# mini_exp_v1-1-0a.net
KiCad netlist of a schematic drawn in EAGLE
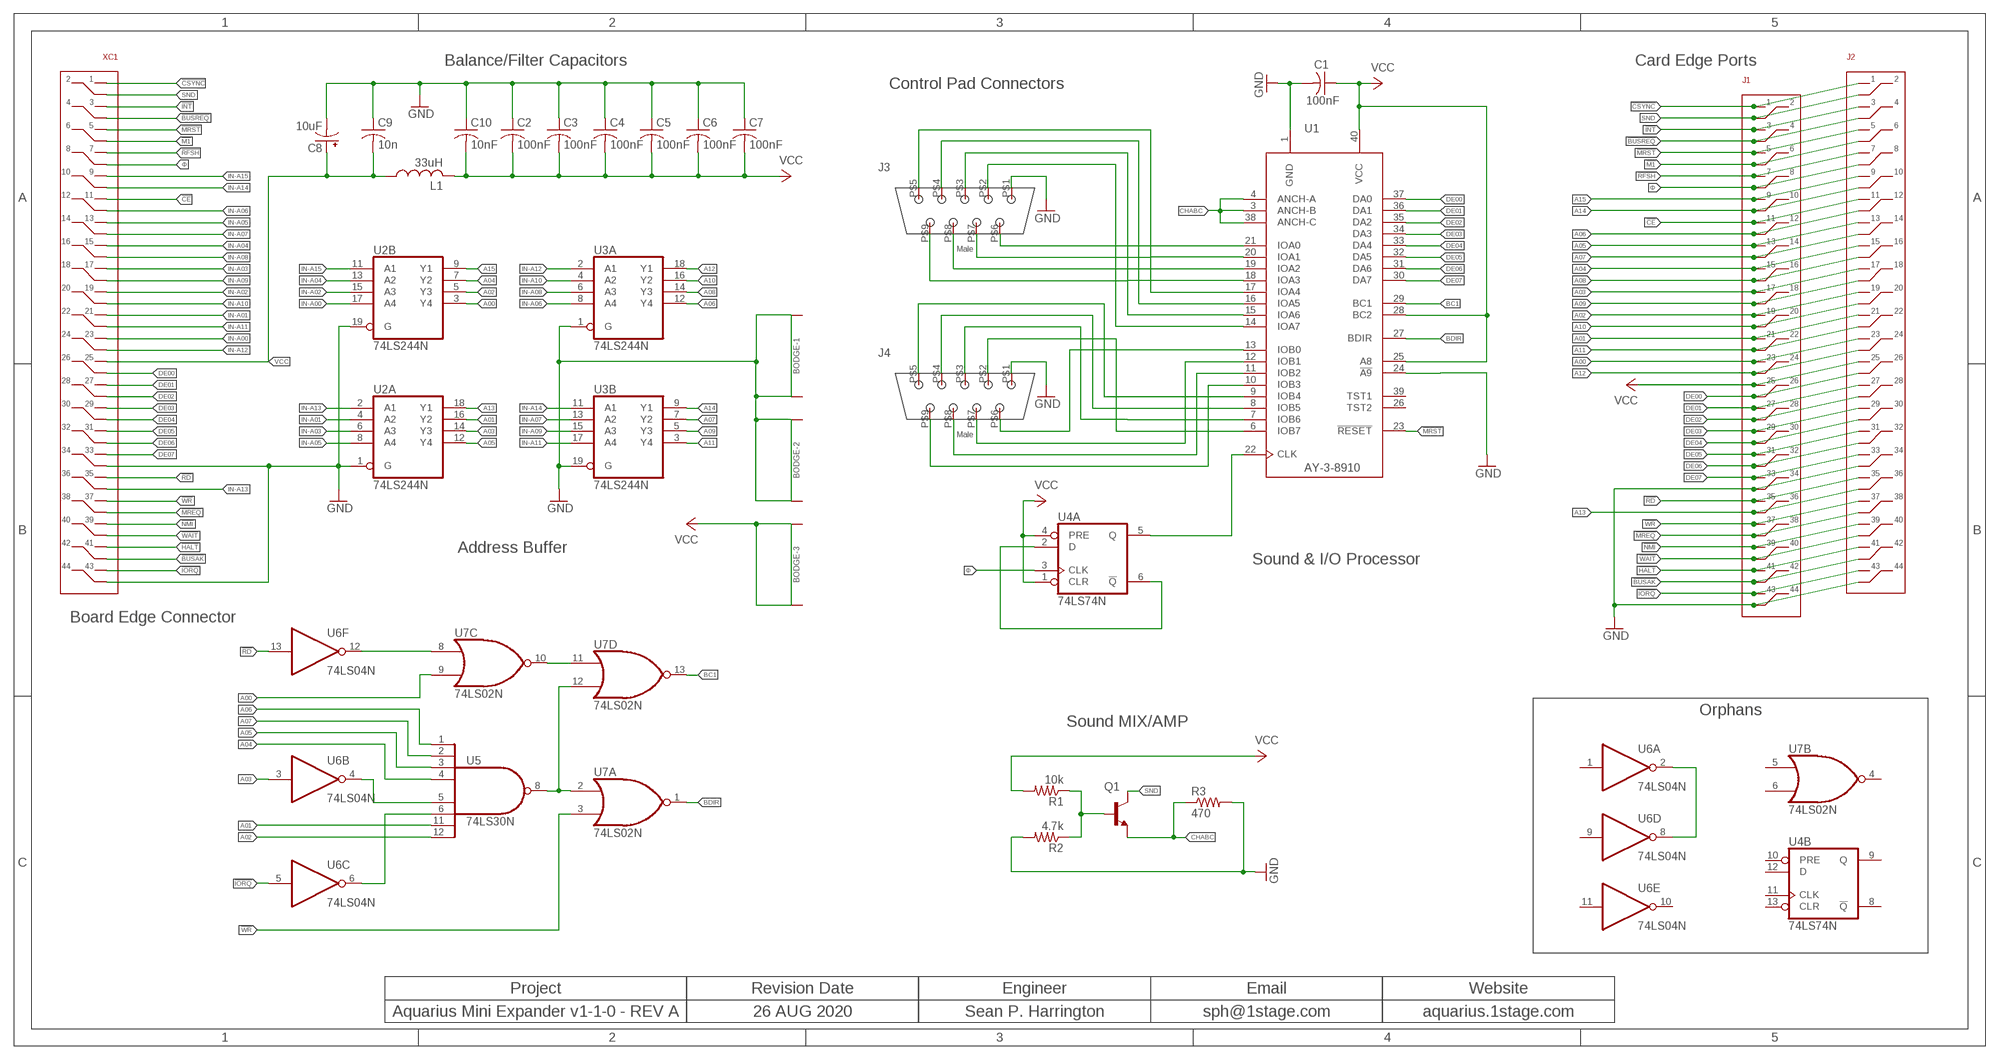
[diagram p0: schematic, sheet 1]

(export (version "E")
  (design (tool "Eeschema 10.0.6"))
  (components
    (comp (ref "C1")
      (value "100nF")
      (footprint "eagle-import:C050-025X095")
      (libsource (lib "eagle-import") (part "C-US050-025X095"))
    )
    (comp (ref "C2")
      (value "100nF")
      (footprint "eagle-import:C050-025X095")
      (libsource (lib "eagle-import") (part "C-US050-025X095"))
    )
    (comp (ref "C3")
      (value "100nF")
      (footprint "eagle-import:C050-025X095")
      (libsource (lib "eagle-import") (part "C-US050-025X095"))
    )
    (comp (ref "C4")
      (value "100nF")
      (footprint "eagle-import:C050-025X095")
      (libsource (lib "eagle-import") (part "C-US050-025X095"))
    )
    (comp (ref "C5")
      (value "100nF")
      (footprint "eagle-import:C050-025X095")
      (libsource (lib "eagle-import") (part "C-US050-025X095"))
    )
    (comp (ref "C6")
      (value "100nF")
      (footprint "eagle-import:C050-025X095")
      (libsource (lib "eagle-import") (part "C-US050-025X095"))
    )
    (comp (ref "C7")
      (value "100nF")
      (footprint "eagle-import:C050-025X095")
      (libsource (lib "eagle-import") (part "C-US050-025X095"))
    )
    (comp (ref "C8")
      (value "10uF")
      (footprint "eagle-import:E22-6")
      (libsource (lib "eagle-import") (part "CPOL-USE22-6AXIAL"))
    )
    (comp (ref "C9")
      (value "10n")
      (footprint "eagle-import:C075-032X103")
      (libsource (lib "eagle-import") (part "C-US075-032X103"))
    )
    (comp (ref "C10")
      (value "10nF")
      (footprint "eagle-import:C075-032X103")
      (libsource (lib "eagle-import") (part "C-US075-032X103"))
    )
    (comp (ref "J1")
      (value "CR22A-44D-2.54DS(70)STRAIGHT")
      (footprint "eagle-import:CR22A-44D-2.54DS(70)")
      (libsource (lib "eagle-import") (part "CR22A-44D-2.54DS(70)STRAIGHT"))
    )
    (comp (ref "J2")
      (value "CR22A-44D-2.54DS(70)STRAIGHT")
      (footprint "eagle-import:CR22A-44D-2.54DS(70)")
      (libsource (lib "eagle-import") (part "CR22A-44D-2.54DS(70)STRAIGHT"))
    )
    (comp (ref "J3")
      (value "DB9-MALE-RA")
      (footprint "eagle-import:DB9-MALE-RA")
      (libsource (lib "eagle-import") (part "DB9-MALE-RA"))
    )
    (comp (ref "J4")
      (value "DB9-MALE-RA")
      (footprint "eagle-import:DB9-MALE-RA")
      (libsource (lib "eagle-import") (part "DB9-MALE-RA"))
    )
    (comp (ref "L1")
      (value "33uH")
      (footprint "eagle-import:0204_5")
      (libsource (lib "eagle-import") (part "L-US0204/5"))
    )
    (comp (ref "Q1")
      (value "-NPN-TO92L")
      (footprint "eagle-import:TO92L")
      (libsource (lib "eagle-import") (part "-NPN-TO92L"))
    )
    (comp (ref "R1")
      (value "10k")
      (footprint "eagle-import:0207_7")
      (libsource (lib "eagle-import") (part "R-US_0207/7"))
    )
    (comp (ref "R2")
      (value "4.7k")
      (footprint "eagle-import:0207_7")
      (libsource (lib "eagle-import") (part "R-US_0207/7"))
    )
    (comp (ref "R3")
      (value "470")
      (footprint "eagle-import:0207_7")
      (libsource (lib "eagle-import") (part "R-US_0207/7"))
    )
    (comp (ref "U1")
      (value "AY-3-8910")
      (footprint "eagle-import:RAD38910-DIL40-6")
      (libsource (lib "eagle-import") (part "RAD38910DIL40-6"))
    )
    (comp (ref "U2")
      (value "74LS244N")
      (footprint "eagle-import:DIL20")
      (libsource (lib "eagle-import") (part "74244NLS"))
    )
    (comp (ref "U3")
      (value "74LS244N")
      (footprint "eagle-import:DIL20")
      (libsource (lib "eagle-import") (part "74244NLS"))
    )
    (comp (ref "U4")
      (value "74LS74N")
      (footprint "eagle-import:DIL14")
      (libsource (lib "eagle-import") (part "7474NLS"))
    )
    (comp (ref "U5")
      (value "74LS30N")
      (footprint "eagle-import:DIL14")
      (libsource (lib "eagle-import") (part "7430NLS"))
    )
    (comp (ref "U6")
      (value "74LS04N")
      (footprint "eagle-import:DIL14")
      (libsource (lib "eagle-import") (part "7404NLS"))
    )
    (comp (ref "U7")
      (value "74LS02N")
      (footprint "eagle-import:DIL14")
      (libsource (lib "eagle-import") (part "7402NLS"))
    )
    (comp (ref "XC1")
      (value "AQ-CART-EDGE")
      (footprint "eagle-import:AQ-CART-EDGE")
      (libsource (lib "eagle-import") (part "AQ-CART-EDGE"))
    )
    (comp (ref "XX01")
      (value "AQ-MX-BODGE-1")
      (footprint "eagle-import:AQ-MX-BODGE-1")
      (libsource (lib "eagle-import") (part "AQ-MX-BODGE-1"))
    )
    (comp (ref "XX02")
      (value "AQ-MX-BODGE-2")
      (footprint "eagle-import:AQ-MX-BODGE-2")
      (libsource (lib "eagle-import") (part "AQ-MX-BODGE-2"))
    )
    (comp (ref "XX03")
      (value "AQ-MX-BODGE-3")
      (footprint "eagle-import:AQ-MX-BODGE-3")
      (libsource (lib "eagle-import") (part "AQ-MX-BODGE-3"))
    )
  )
  (nets
    (net (code "1") (name "/~{BUSAK}") (class "Default")
      (node (ref "J1") (pin "P$42") (pinfunction "X42_P$42") (pintype "bidirectional"))
      (node (ref "J2") (pin "P$42") (pinfunction "X42_P$42") (pintype "bidirectional"))
      (node (ref "XC1") (pin "P$42") (pinfunction "X42_P$42") (pintype "bidirectional"))
    )
    (net (code "2") (name "/~{BUSREQ}") (class "Default")
      (node (ref "J1") (pin "P$4") (pinfunction "X4_P$4") (pintype "bidirectional"))
      (node (ref "J2") (pin "P$4") (pinfunction "X4_P$4") (pintype "bidirectional"))
      (node (ref "XC1") (pin "P$4") (pinfunction "X4_P$4") (pintype "bidirectional"))
    )
    (net (code "3") (name "/~{CE}") (class "Default")
      (node (ref "J1") (pin "P$11") (pinfunction "X11_P$11") (pintype "bidirectional"))
      (node (ref "J2") (pin "P$11") (pinfunction "X11_P$11") (pintype "bidirectional"))
      (node (ref "XC1") (pin "P$11") (pinfunction "X11_P$11") (pintype "bidirectional"))
    )
    (net (code "4") (name "/~{CSYNC}") (class "Default")
      (node (ref "J1") (pin "P$1") (pinfunction "X1_P$1") (pintype "bidirectional"))
      (node (ref "J2") (pin "P$1") (pinfunction "X1_P$1") (pintype "bidirectional"))
      (node (ref "XC1") (pin "P$1") (pinfunction "X1_P$1") (pintype "bidirectional"))
    )
    (net (code "5") (name "/~{HALT}") (class "Default")
      (node (ref "J1") (pin "P$41") (pinfunction "X41_P$41") (pintype "bidirectional"))
      (node (ref "J2") (pin "P$41") (pinfunction "X41_P$41") (pintype "bidirectional"))
      (node (ref "XC1") (pin "P$41") (pinfunction "X41_P$41") (pintype "bidirectional"))
    )
    (net (code "6") (name "/~{INT}") (class "Default")
      (node (ref "J1") (pin "P$3") (pinfunction "X3_P$3") (pintype "bidirectional"))
      (node (ref "J2") (pin "P$3") (pinfunction "X3_P$3") (pintype "bidirectional"))
      (node (ref "XC1") (pin "P$3") (pinfunction "X3_P$3") (pintype "bidirectional"))
    )
    (net (code "7") (name "/~{IORQ}") (class "Default")
      (node (ref "J1") (pin "P$43") (pinfunction "X43_P$43") (pintype "bidirectional"))
      (node (ref "J2") (pin "P$43") (pinfunction "X43_P$43") (pintype "bidirectional"))
      (node (ref "U6") (pin "5") (pinfunction "I_5") (pintype "input"))
      (node (ref "XC1") (pin "P$43") (pinfunction "X43_P$43") (pintype "bidirectional"))
    )
    (net (code "8") (name "/~{M1}") (class "Default")
      (node (ref "J1") (pin "P$6") (pinfunction "X6_P$6") (pintype "bidirectional"))
      (node (ref "J2") (pin "P$6") (pinfunction "X6_P$6") (pintype "bidirectional"))
      (node (ref "XC1") (pin "P$6") (pinfunction "X6_P$6") (pintype "bidirectional"))
    )
    (net (code "9") (name "/~{MREQ}") (class "Default")
      (node (ref "J1") (pin "P$38") (pinfunction "X38_P$38") (pintype "bidirectional"))
      (node (ref "J2") (pin "P$38") (pinfunction "X38_P$38") (pintype "bidirectional"))
      (node (ref "XC1") (pin "P$38") (pinfunction "X38_P$38") (pintype "bidirectional"))
    )
    (net (code "10") (name "/~{MRST}") (class "Default")
      (node (ref "J1") (pin "P$5") (pinfunction "X5_P$5") (pintype "bidirectional"))
      (node (ref "J2") (pin "P$5") (pinfunction "X5_P$5") (pintype "bidirectional"))
      (node (ref "U1") (pin "23") (pinfunction "~{RESET}_23") (pintype "bidirectional"))
      (node (ref "XC1") (pin "P$5") (pinfunction "X5_P$5") (pintype "bidirectional"))
    )
    (net (code "11") (name "/~{NMI}") (class "Default")
      (node (ref "J1") (pin "P$39") (pinfunction "X39_P$39") (pintype "bidirectional"))
      (node (ref "J2") (pin "P$39") (pinfunction "X39_P$39") (pintype "bidirectional"))
      (node (ref "XC1") (pin "P$39") (pinfunction "X39_P$39") (pintype "bidirectional"))
    )
    (net (code "12") (name "/~{RD}") (class "Default")
      (node (ref "J1") (pin "P$35") (pinfunction "X35_P$35") (pintype "bidirectional"))
      (node (ref "J2") (pin "P$35") (pinfunction "X35_P$35") (pintype "bidirectional"))
      (node (ref "U6") (pin "13") (pinfunction "I_13") (pintype "input"))
      (node (ref "XC1") (pin "P$35") (pinfunction "X35_P$35") (pintype "bidirectional"))
    )
    (net (code "13") (name "/~{RFSH}") (class "Default")
      (node (ref "J1") (pin "P$7") (pinfunction "X7_P$7") (pintype "bidirectional"))
      (node (ref "J2") (pin "P$7") (pinfunction "X7_P$7") (pintype "bidirectional"))
      (node (ref "XC1") (pin "P$7") (pinfunction "X7_P$7") (pintype "bidirectional"))
    )
    (net (code "14") (name "/~{WAIT}") (class "Default")
      (node (ref "J1") (pin "P$40") (pinfunction "X40_P$40") (pintype "bidirectional"))
      (node (ref "J2") (pin "P$40") (pinfunction "X40_P$40") (pintype "bidirectional"))
      (node (ref "XC1") (pin "P$40") (pinfunction "X40_P$40") (pintype "bidirectional"))
    )
    (net (code "15") (name "/~{WR}") (class "Default")
      (node (ref "J1") (pin "P$37") (pinfunction "X37_P$37") (pintype "bidirectional"))
      (node (ref "J2") (pin "P$37") (pinfunction "X37_P$37") (pintype "bidirectional"))
      (node (ref "U7") (pin "3") (pinfunction "I1_3") (pintype "input"))
      (node (ref "XC1") (pin "P$37") (pinfunction "X37_P$37") (pintype "bidirectional"))
    )
    (net (code "16") (name "A00") (class "Default")
      (node (ref "J1") (pin "P$23") (pinfunction "X23_P$23") (pintype "bidirectional"))
      (node (ref "J2") (pin "P$23") (pinfunction "X23_P$23") (pintype "bidirectional"))
      (node (ref "U2") (pin "3") (pinfunction "Y4_3") (pintype "tri_state"))
      (node (ref "U7") (pin "9") (pinfunction "I1_9") (pintype "input"))
    )
    (net (code "17") (name "A01") (class "Default")
      (node (ref "J1") (pin "P$21") (pinfunction "X21_P$21") (pintype "bidirectional"))
      (node (ref "J2") (pin "P$21") (pinfunction "X21_P$21") (pintype "bidirectional"))
      (node (ref "U2") (pin "16") (pinfunction "Y2_16") (pintype "tri_state"))
      (node (ref "U5") (pin "11") (pinfunction "I6_11") (pintype "input"))
    )
    (net (code "18") (name "A02") (class "Default")
      (node (ref "J1") (pin "P$19") (pinfunction "X19_P$19") (pintype "bidirectional"))
      (node (ref "J2") (pin "P$19") (pinfunction "X19_P$19") (pintype "bidirectional"))
      (node (ref "U2") (pin "5") (pinfunction "Y3_5") (pintype "tri_state"))
      (node (ref "U5") (pin "12") (pinfunction "I7_12") (pintype "input"))
    )
    (net (code "19") (name "A03") (class "Default")
      (node (ref "J1") (pin "P$17") (pinfunction "X17_P$17") (pintype "bidirectional"))
      (node (ref "J2") (pin "P$17") (pinfunction "X17_P$17") (pintype "bidirectional"))
      (node (ref "U2") (pin "14") (pinfunction "Y3_14") (pintype "tri_state"))
      (node (ref "U6") (pin "3") (pinfunction "I_3") (pintype "input"))
    )
    (net (code "20") (name "A04") (class "Default")
      (node (ref "J1") (pin "P$15") (pinfunction "X15_P$15") (pintype "bidirectional"))
      (node (ref "J2") (pin "P$15") (pinfunction "X15_P$15") (pintype "bidirectional"))
      (node (ref "U2") (pin "7") (pinfunction "Y2_7") (pintype "tri_state"))
      (node (ref "U5") (pin "4") (pinfunction "I3_4") (pintype "input"))
    )
    (net (code "21") (name "A05") (class "Default")
      (node (ref "J1") (pin "P$13") (pinfunction "X13_P$13") (pintype "bidirectional"))
      (node (ref "J2") (pin "P$13") (pinfunction "X13_P$13") (pintype "bidirectional"))
      (node (ref "U2") (pin "12") (pinfunction "Y4_12") (pintype "tri_state"))
      (node (ref "U5") (pin "3") (pinfunction "I2_3") (pintype "input"))
    )
    (net (code "22") (name "A06") (class "Default")
      (node (ref "J1") (pin "P$12") (pinfunction "X12_P$12") (pintype "bidirectional"))
      (node (ref "J2") (pin "P$12") (pinfunction "X12_P$12") (pintype "bidirectional"))
      (node (ref "U3") (pin "12") (pinfunction "Y4_12") (pintype "tri_state"))
      (node (ref "U5") (pin "1") (pinfunction "I0_1") (pintype "input"))
    )
    (net (code "23") (name "A07") (class "Default")
      (node (ref "J1") (pin "P$14") (pinfunction "X14_P$14") (pintype "bidirectional"))
      (node (ref "J2") (pin "P$14") (pinfunction "X14_P$14") (pintype "bidirectional"))
      (node (ref "U3") (pin "7") (pinfunction "Y2_7") (pintype "tri_state"))
      (node (ref "U5") (pin "2") (pinfunction "I1_2") (pintype "input"))
    )
    (net (code "24") (name "A08") (class "Default")
      (node (ref "J1") (pin "P$16") (pinfunction "X16_P$16") (pintype "bidirectional"))
      (node (ref "J2") (pin "P$16") (pinfunction "X16_P$16") (pintype "bidirectional"))
      (node (ref "U3") (pin "14") (pinfunction "Y3_14") (pintype "tri_state"))
    )
    (net (code "25") (name "A09") (class "Default")
      (node (ref "J1") (pin "P$18") (pinfunction "X18_P$18") (pintype "bidirectional"))
      (node (ref "J2") (pin "P$18") (pinfunction "X18_P$18") (pintype "bidirectional"))
      (node (ref "U3") (pin "5") (pinfunction "Y3_5") (pintype "tri_state"))
    )
    (net (code "26") (name "A10") (class "Default")
      (node (ref "J1") (pin "P$20") (pinfunction "X20_P$20") (pintype "bidirectional"))
      (node (ref "J2") (pin "P$20") (pinfunction "X20_P$20") (pintype "bidirectional"))
      (node (ref "U3") (pin "16") (pinfunction "Y2_16") (pintype "tri_state"))
    )
    (net (code "27") (name "A11") (class "Default")
      (node (ref "J1") (pin "P$22") (pinfunction "X22_P$22") (pintype "bidirectional"))
      (node (ref "J2") (pin "P$22") (pinfunction "X22_P$22") (pintype "bidirectional"))
      (node (ref "U3") (pin "3") (pinfunction "Y4_3") (pintype "tri_state"))
    )
    (net (code "28") (name "A12") (class "Default")
      (node (ref "J1") (pin "P$24") (pinfunction "X24_P$24") (pintype "bidirectional"))
      (node (ref "J2") (pin "P$24") (pinfunction "X24_P$24") (pintype "bidirectional"))
      (node (ref "U3") (pin "18") (pinfunction "Y1_18") (pintype "tri_state"))
    )
    (net (code "29") (name "A13") (class "Default")
      (node (ref "J1") (pin "P$36") (pinfunction "X36_P$36") (pintype "bidirectional"))
      (node (ref "J2") (pin "P$36") (pinfunction "X36_P$36") (pintype "bidirectional"))
      (node (ref "U2") (pin "18") (pinfunction "Y1_18") (pintype "tri_state"))
    )
    (net (code "30") (name "A14") (class "Default")
      (node (ref "J1") (pin "P$10") (pinfunction "X10_P$10") (pintype "bidirectional"))
      (node (ref "J2") (pin "P$10") (pinfunction "X10_P$10") (pintype "bidirectional"))
      (node (ref "U3") (pin "9") (pinfunction "Y1_9") (pintype "tri_state"))
    )
    (net (code "31") (name "A15") (class "Default")
      (node (ref "J1") (pin "P$9") (pinfunction "X9_P$9") (pintype "bidirectional"))
      (node (ref "J2") (pin "P$9") (pinfunction "X9_P$9") (pintype "bidirectional"))
      (node (ref "U2") (pin "9") (pinfunction "Y1_9") (pintype "tri_state"))
    )
    (net (code "32") (name "BC1") (class "Default")
      (node (ref "U1") (pin "29") (pinfunction "BC1_29") (pintype "bidirectional"))
      (node (ref "U7") (pin "13") (pinfunction "O_13") (pintype "output"))
    )
    (net (code "33") (name "BDIR") (class "Default")
      (node (ref "U1") (pin "27") (pinfunction "BDIR_27") (pintype "bidirectional"))
      (node (ref "U7") (pin "1") (pinfunction "O_1") (pintype "output"))
    )
    (net (code "34") (name "CHABC") (class "Default")
      (node (ref "Q1") (pin "1") (pinfunction "E_1") (pintype "passive"))
      (node (ref "R3") (pin "1") (pinfunction "1_1") (pintype "passive"))
      (node (ref "U1") (pin "3") (pinfunction "ANCH-B_3") (pintype "bidirectional"))
      (node (ref "U1") (pin "38") (pinfunction "ANCH-C_38") (pintype "bidirectional"))
      (node (ref "U1") (pin "4") (pinfunction "ANCH-A_4") (pintype "bidirectional"))
    )
    (net (code "35") (name "DE00") (class "Default")
      (node (ref "J1") (pin "P$26") (pinfunction "X26_P$26") (pintype "bidirectional"))
      (node (ref "J2") (pin "P$26") (pinfunction "X26_P$26") (pintype "bidirectional"))
      (node (ref "U1") (pin "37") (pinfunction "DA0_37") (pintype "bidirectional"))
      (node (ref "XC1") (pin "P$26") (pinfunction "X26_P$26") (pintype "bidirectional"))
    )
    (net (code "36") (name "DE01") (class "Default")
      (node (ref "J1") (pin "P$27") (pinfunction "X27_P$27") (pintype "bidirectional"))
      (node (ref "J2") (pin "P$27") (pinfunction "X27_P$27") (pintype "bidirectional"))
      (node (ref "U1") (pin "36") (pinfunction "DA1_36") (pintype "bidirectional"))
      (node (ref "XC1") (pin "P$27") (pinfunction "X27_P$27") (pintype "bidirectional"))
    )
    (net (code "37") (name "DE02") (class "Default")
      (node (ref "J1") (pin "P$28") (pinfunction "X28_P$28") (pintype "bidirectional"))
      (node (ref "J2") (pin "P$28") (pinfunction "X28_P$28") (pintype "bidirectional"))
      (node (ref "U1") (pin "35") (pinfunction "DA2_35") (pintype "bidirectional"))
      (node (ref "XC1") (pin "P$28") (pinfunction "X28_P$28") (pintype "bidirectional"))
    )
    (net (code "38") (name "DE03") (class "Default")
      (node (ref "J1") (pin "P$29") (pinfunction "X29_P$29") (pintype "bidirectional"))
      (node (ref "J2") (pin "P$29") (pinfunction "X29_P$29") (pintype "bidirectional"))
      (node (ref "U1") (pin "34") (pinfunction "DA3_34") (pintype "bidirectional"))
      (node (ref "XC1") (pin "P$29") (pinfunction "X29_P$29") (pintype "bidirectional"))
    )
    (net (code "39") (name "DE04") (class "Default")
      (node (ref "J1") (pin "P$30") (pinfunction "X30_P$30") (pintype "bidirectional"))
      (node (ref "J2") (pin "P$30") (pinfunction "X30_P$30") (pintype "bidirectional"))
      (node (ref "U1") (pin "33") (pinfunction "DA4_33") (pintype "bidirectional"))
      (node (ref "XC1") (pin "P$30") (pinfunction "X30_P$30") (pintype "bidirectional"))
    )
    (net (code "40") (name "DE05") (class "Default")
      (node (ref "J1") (pin "P$31") (pinfunction "X31_P$31") (pintype "bidirectional"))
      (node (ref "J2") (pin "P$31") (pinfunction "X31_P$31") (pintype "bidirectional"))
      (node (ref "U1") (pin "32") (pinfunction "DA5_32") (pintype "bidirectional"))
      (node (ref "XC1") (pin "P$31") (pinfunction "X31_P$31") (pintype "bidirectional"))
    )
    (net (code "41") (name "DE06") (class "Default")
      (node (ref "J1") (pin "P$32") (pinfunction "X32_P$32") (pintype "bidirectional"))
      (node (ref "J2") (pin "P$32") (pinfunction "X32_P$32") (pintype "bidirectional"))
      (node (ref "U1") (pin "31") (pinfunction "DA6_31") (pintype "bidirectional"))
      (node (ref "XC1") (pin "P$32") (pinfunction "X32_P$32") (pintype "bidirectional"))
    )
    (net (code "42") (name "DE07") (class "Default")
      (node (ref "J1") (pin "P$33") (pinfunction "X33_P$33") (pintype "bidirectional"))
      (node (ref "J2") (pin "P$33") (pinfunction "X33_P$33") (pintype "bidirectional"))
      (node (ref "U1") (pin "30") (pinfunction "DA7_30") (pintype "bidirectional"))
      (node (ref "XC1") (pin "P$33") (pinfunction "X33_P$33") (pintype "bidirectional"))
    )
    (net (code "43") (name "GND") (class "Default")
      (node (ref "C1") (pin "2") (pinfunction "2_2") (pintype "passive"))
      (node (ref "C10") (pin "1") (pinfunction "1_1") (pintype "passive"))
      (node (ref "C2") (pin "1") (pinfunction "1_1") (pintype "passive"))
      (node (ref "C3") (pin "1") (pinfunction "1_1") (pintype "passive"))
      (node (ref "C4") (pin "1") (pinfunction "1_1") (pintype "passive"))
      (node (ref "C5") (pin "1") (pinfunction "1_1") (pintype "passive"))
      (node (ref "C6") (pin "1") (pinfunction "1_1") (pintype "passive"))
      (node (ref "C7") (pin "1") (pinfunction "1_1") (pintype "passive"))
      (node (ref "C8") (pin "-") (pinfunction "-_-") (pintype "passive"))
      (node (ref "C9") (pin "1") (pinfunction "1_1") (pintype "passive"))
      (node (ref "J1") (pin "P$34") (pinfunction "X34_P$34") (pintype "bidirectional"))
      (node (ref "J1") (pin "P$44") (pinfunction "X44_P$44") (pintype "bidirectional"))
      (node (ref "J2") (pin "P$34") (pinfunction "X34_P$34") (pintype "bidirectional"))
      (node (ref "J2") (pin "P$44") (pinfunction "X44_P$44") (pintype "bidirectional"))
      (node (ref "J3") (pin "P$1") (pinfunction "P$1_P$1") (pintype "bidirectional"))
      (node (ref "J4") (pin "P$1") (pinfunction "P$1_P$1") (pintype "bidirectional"))
      (node (ref "R2") (pin "2") (pinfunction "2_2") (pintype "passive"))
      (node (ref "R3") (pin "2") (pinfunction "2_2") (pintype "passive"))
      (node (ref "U1") (pin "1") (pinfunction "GND_1") (pintype "power_in"))
      (node (ref "U1") (pin "24") (pinfunction "~{A9}_24") (pintype "bidirectional"))
      (node (ref "U2") (pin "1") (pinfunction "G_1") (pintype "input"))
      (node (ref "U2") (pin "19") (pinfunction "G_19") (pintype "input"))
      (node (ref "U3") (pin "1") (pinfunction "G_1") (pintype "input"))
      (node (ref "U3") (pin "19") (pinfunction "G_19") (pintype "input"))
      (node (ref "XC1") (pin "P$34") (pinfunction "X34_P$34") (pintype "bidirectional"))
      (node (ref "XC1") (pin "P$44") (pinfunction "X44_P$44") (pintype "bidirectional"))
      (node (ref "XX01") (pin "P$1") (pinfunction "P$1_P$1") (pintype "bidirectional"))
      (node (ref "XX01") (pin "P$2") (pinfunction "P$2_P$2") (pintype "bidirectional"))
      (node (ref "XX02") (pin "P$1") (pinfunction "P$1_P$1") (pintype "bidirectional"))
      (node (ref "XX02") (pin "P$2") (pinfunction "P$2_P$2") (pintype "bidirectional"))
    )
    (net (code "44") (name "IN-A00") (class "Default")
      (node (ref "U2") (pin "17") (pinfunction "A4_17") (pintype "input"))
      (node (ref "XC1") (pin "P$23") (pinfunction "X23_P$23") (pintype "bidirectional"))
    )
    (net (code "45") (name "IN-A01") (class "Default")
      (node (ref "U2") (pin "4") (pinfunction "A2_4") (pintype "input"))
      (node (ref "XC1") (pin "P$21") (pinfunction "X21_P$21") (pintype "bidirectional"))
    )
    (net (code "46") (name "IN-A02") (class "Default")
      (node (ref "U2") (pin "15") (pinfunction "A3_15") (pintype "input"))
      (node (ref "XC1") (pin "P$19") (pinfunction "X19_P$19") (pintype "bidirectional"))
    )
    (net (code "47") (name "IN-A03") (class "Default")
      (node (ref "U2") (pin "6") (pinfunction "A3_6") (pintype "input"))
      (node (ref "XC1") (pin "P$17") (pinfunction "X17_P$17") (pintype "bidirectional"))
    )
    (net (code "48") (name "IN-A04") (class "Default")
      (node (ref "U2") (pin "13") (pinfunction "A2_13") (pintype "input"))
      (node (ref "XC1") (pin "P$15") (pinfunction "X15_P$15") (pintype "bidirectional"))
    )
    (net (code "49") (name "IN-A05") (class "Default")
      (node (ref "U2") (pin "8") (pinfunction "A4_8") (pintype "input"))
      (node (ref "XC1") (pin "P$13") (pinfunction "X13_P$13") (pintype "bidirectional"))
    )
    (net (code "50") (name "IN-A06") (class "Default")
      (node (ref "U3") (pin "8") (pinfunction "A4_8") (pintype "input"))
      (node (ref "XC1") (pin "P$12") (pinfunction "X12_P$12") (pintype "bidirectional"))
    )
    (net (code "51") (name "IN-A07") (class "Default")
      (node (ref "U3") (pin "13") (pinfunction "A2_13") (pintype "input"))
      (node (ref "XC1") (pin "P$14") (pinfunction "X14_P$14") (pintype "bidirectional"))
    )
    (net (code "52") (name "IN-A08") (class "Default")
      (node (ref "U3") (pin "6") (pinfunction "A3_6") (pintype "input"))
      (node (ref "XC1") (pin "P$16") (pinfunction "X16_P$16") (pintype "bidirectional"))
    )
    (net (code "53") (name "IN-A09") (class "Default")
      (node (ref "U3") (pin "15") (pinfunction "A3_15") (pintype "input"))
      (node (ref "XC1") (pin "P$18") (pinfunction "X18_P$18") (pintype "bidirectional"))
    )
    (net (code "54") (name "IN-A10") (class "Default")
      (node (ref "U3") (pin "4") (pinfunction "A2_4") (pintype "input"))
      (node (ref "XC1") (pin "P$20") (pinfunction "X20_P$20") (pintype "bidirectional"))
    )
    (net (code "55") (name "IN-A11") (class "Default")
      (node (ref "U3") (pin "17") (pinfunction "A4_17") (pintype "input"))
      (node (ref "XC1") (pin "P$22") (pinfunction "X22_P$22") (pintype "bidirectional"))
    )
    (net (code "56") (name "IN-A12") (class "Default")
      (node (ref "U3") (pin "2") (pinfunction "A1_2") (pintype "input"))
      (node (ref "XC1") (pin "P$24") (pinfunction "X24_P$24") (pintype "bidirectional"))
    )
    (net (code "57") (name "IN-A13") (class "Default")
      (node (ref "U2") (pin "2") (pinfunction "A1_2") (pintype "input"))
      (node (ref "XC1") (pin "P$36") (pinfunction "X36_P$36") (pintype "bidirectional"))
    )
    (net (code "58") (name "IN-A14") (class "Default")
      (node (ref "U3") (pin "11") (pinfunction "A1_11") (pintype "input"))
      (node (ref "XC1") (pin "P$10") (pinfunction "X10_P$10") (pintype "bidirectional"))
    )
    (net (code "59") (name "IN-A15") (class "Default")
      (node (ref "U2") (pin "11") (pinfunction "A1_11") (pintype "input"))
      (node (ref "XC1") (pin "P$9") (pinfunction "X9_P$9") (pintype "bidirectional"))
    )
    (net (code "60") (name "Net-(Q1-B)") (class "Default")
      (node (ref "Q1") (pin "2") (pinfunction "B_2") (pintype "passive"))
      (node (ref "R1") (pin "1") (pinfunction "1_1") (pintype "passive"))
      (node (ref "R2") (pin "1") (pinfunction "1_1") (pintype "passive"))
    )
    (net (code "61") (name "Net-(U1-CLK)") (class "Default")
      (node (ref "U1") (pin "22") (pinfunction "CLK_22") (pintype "input"))
      (node (ref "U4") (pin "5") (pinfunction "Q_5") (pintype "output"))
    )
    (net (code "62") (name "Net-(U1-IOA0)") (class "Default")
      (node (ref "J3") (pin "P$6") (pinfunction "P$6_P$6") (pintype "bidirectional"))
      (node (ref "U1") (pin "21") (pinfunction "IOA0_21") (pintype "bidirectional"))
    )
    (net (code "63") (name "Net-(U1-IOA1)") (class "Default")
      (node (ref "J3") (pin "P$7") (pinfunction "P$7_P$7") (pintype "bidirectional"))
      (node (ref "U1") (pin "20") (pinfunction "IOA1_20") (pintype "bidirectional"))
    )
    (net (code "64") (name "Net-(U1-IOA2)") (class "Default")
      (node (ref "J3") (pin "P$8") (pinfunction "P$8_P$8") (pintype "bidirectional"))
      (node (ref "U1") (pin "19") (pinfunction "IOA2_19") (pintype "bidirectional"))
    )
    (net (code "65") (name "Net-(U1-IOA3)") (class "Default")
      (node (ref "J3") (pin "P$9") (pinfunction "P$9_P$9") (pintype "bidirectional"))
      (node (ref "U1") (pin "18") (pinfunction "IOA3_18") (pintype "bidirectional"))
    )
    (net (code "66") (name "Net-(U1-IOA4)") (class "Default")
      (node (ref "J3") (pin "P$5") (pinfunction "P$5_P$5") (pintype "bidirectional"))
      (node (ref "U1") (pin "17") (pinfunction "IOA4_17") (pintype "bidirectional"))
    )
    (net (code "67") (name "Net-(U1-IOA5)") (class "Default")
      (node (ref "J3") (pin "P$4") (pinfunction "P$4_P$4") (pintype "bidirectional"))
      (node (ref "U1") (pin "16") (pinfunction "IOA5_16") (pintype "bidirectional"))
    )
    (net (code "68") (name "Net-(U1-IOA6)") (class "Default")
      (node (ref "J3") (pin "P$3") (pinfunction "P$3_P$3") (pintype "bidirectional"))
      (node (ref "U1") (pin "15") (pinfunction "IOA6_15") (pintype "bidirectional"))
    )
    (net (code "69") (name "Net-(U1-IOA7)") (class "Default")
      (node (ref "J3") (pin "P$2") (pinfunction "P$2_P$2") (pintype "bidirectional"))
      (node (ref "U1") (pin "14") (pinfunction "IOA7_14") (pintype "bidirectional"))
    )
    (net (code "70") (name "Net-(U1-IOB0)") (class "Default")
      (node (ref "J4") (pin "P$6") (pinfunction "P$6_P$6") (pintype "bidirectional"))
      (node (ref "U1") (pin "13") (pinfunction "IOB0_13") (pintype "bidirectional"))
    )
    (net (code "71") (name "Net-(U1-IOB1)") (class "Default")
      (node (ref "J4") (pin "P$7") (pinfunction "P$7_P$7") (pintype "bidirectional"))
      (node (ref "U1") (pin "12") (pinfunction "IOB1_12") (pintype "bidirectional"))
    )
    (net (code "72") (name "Net-(U1-IOB2)") (class "Default")
      (node (ref "J4") (pin "P$8") (pinfunction "P$8_P$8") (pintype "bidirectional"))
      (node (ref "U1") (pin "11") (pinfunction "IOB2_11") (pintype "bidirectional"))
    )
    (net (code "73") (name "Net-(U1-IOB3)") (class "Default")
      (node (ref "J4") (pin "P$9") (pinfunction "P$9_P$9") (pintype "bidirectional"))
      (node (ref "U1") (pin "10") (pinfunction "IOB3_10") (pintype "bidirectional"))
    )
    (net (code "74") (name "Net-(U1-IOB4)") (class "Default")
      (node (ref "J4") (pin "P$5") (pinfunction "P$5_P$5") (pintype "bidirectional"))
      (node (ref "U1") (pin "9") (pinfunction "IOB4_9") (pintype "bidirectional"))
    )
    (net (code "75") (name "Net-(U1-IOB5)") (class "Default")
      (node (ref "J4") (pin "P$4") (pinfunction "P$4_P$4") (pintype "bidirectional"))
      (node (ref "U1") (pin "8") (pinfunction "IOB5_8") (pintype "bidirectional"))
    )
    (net (code "76") (name "Net-(U1-IOB6)") (class "Default")
      (node (ref "J4") (pin "P$3") (pinfunction "P$3_P$3") (pintype "bidirectional"))
      (node (ref "U1") (pin "7") (pinfunction "IOB6_7") (pintype "bidirectional"))
    )
    (net (code "77") (name "Net-(U1-IOB7)") (class "Default")
      (node (ref "J4") (pin "P$2") (pinfunction "P$2_P$2") (pintype "bidirectional"))
      (node (ref "U1") (pin "6") (pinfunction "IOB7_6") (pintype "bidirectional"))
    )
    (net (code "78") (name "Net-(U4A-D)") (class "Default")
      (node (ref "U4") (pin "2") (pinfunction "D_2") (pintype "input"))
      (node (ref "U4") (pin "6") (pinfunction "~{Q}_6") (pintype "output"))
    )
    (net (code "79") (name "Net-(U5A-I4)") (class "Default")
      (node (ref "U5") (pin "5") (pinfunction "I4_5") (pintype "input"))
      (node (ref "U6") (pin "4") (pinfunction "O_4") (pintype "output"))
    )
    (net (code "80") (name "Net-(U5A-I5)") (class "Default")
      (node (ref "U5") (pin "6") (pinfunction "I5_6") (pintype "input"))
      (node (ref "U6") (pin "6") (pinfunction "O_6") (pintype "output"))
    )
    (net (code "81") (name "Net-(U5A-O)") (class "Default")
      (node (ref "U5") (pin "8") (pinfunction "O_8") (pintype "output"))
      (node (ref "U7") (pin "12") (pinfunction "I1_12") (pintype "input"))
      (node (ref "U7") (pin "2") (pinfunction "I0_2") (pintype "input"))
    )
    (net (code "82") (name "Net-(U6A-O)") (class "Default")
      (node (ref "U6") (pin "2") (pinfunction "O_2") (pintype "output"))
      (node (ref "U6") (pin "8") (pinfunction "O_8") (pintype "output"))
    )
    (net (code "83") (name "Net-(U6F-O)") (class "Default")
      (node (ref "U6") (pin "12") (pinfunction "O_12") (pintype "output"))
      (node (ref "U7") (pin "8") (pinfunction "I0_8") (pintype "input"))
    )
    (net (code "84") (name "Net-(U7C-O)") (class "Default")
      (node (ref "U7") (pin "10") (pinfunction "O_10") (pintype "output"))
      (node (ref "U7") (pin "11") (pinfunction "I0_11") (pintype "input"))
    )
    (net (code "85") (name "SND") (class "Default")
      (node (ref "J1") (pin "P$2") (pinfunction "X2_P$2") (pintype "bidirectional"))
      (node (ref "J2") (pin "P$2") (pinfunction "X2_P$2") (pintype "bidirectional"))
      (node (ref "Q1") (pin "3") (pinfunction "C_3") (pintype "passive"))
      (node (ref "XC1") (pin "P$2") (pinfunction "X2_P$2") (pintype "bidirectional"))
    )
    (net (code "86") (name "VCC") (class "Default")
      (node (ref "C1") (pin "1") (pinfunction "1_1") (pintype "passive"))
      (node (ref "C10") (pin "2") (pinfunction "2_2") (pintype "passive"))
      (node (ref "C2") (pin "2") (pinfunction "2_2") (pintype "passive"))
      (node (ref "C3") (pin "2") (pinfunction "2_2") (pintype "passive"))
      (node (ref "C4") (pin "2") (pinfunction "2_2") (pintype "passive"))
      (node (ref "C5") (pin "2") (pinfunction "2_2") (pintype "passive"))
      (node (ref "C6") (pin "2") (pinfunction "2_2") (pintype "passive"))
      (node (ref "C7") (pin "2") (pinfunction "2_2") (pintype "passive"))
      (node (ref "C8") (pin "+") (pinfunction "+_+") (pintype "passive"))
      (node (ref "C9") (pin "2") (pinfunction "2_2") (pintype "passive"))
      (node (ref "J1") (pin "P$25") (pinfunction "X25_P$25") (pintype "bidirectional"))
      (node (ref "J2") (pin "P$25") (pinfunction "X25_P$25") (pintype "bidirectional"))
      (node (ref "L1") (pin "1") (pinfunction "1_1") (pintype "passive"))
      (node (ref "L1") (pin "2") (pinfunction "2_2") (pintype "passive"))
      (node (ref "R1") (pin "2") (pinfunction "2_2") (pintype "passive"))
      (node (ref "U1") (pin "25") (pinfunction "A8_25") (pintype "bidirectional"))
      (node (ref "U1") (pin "28") (pinfunction "BC2_28") (pintype "bidirectional"))
      (node (ref "U1") (pin "40") (pinfunction "VCC_40") (pintype "power_in"))
      (node (ref "U4") (pin "1") (pinfunction "CLR_1") (pintype "input"))
      (node (ref "U4") (pin "4") (pinfunction "PRE_4") (pintype "input"))
      (node (ref "XC1") (pin "P$25") (pinfunction "X25_P$25") (pintype "bidirectional"))
      (node (ref "XX03") (pin "P$1") (pinfunction "P$1_P$1") (pintype "bidirectional"))
      (node (ref "XX03") (pin "P$2") (pinfunction "P$2_P$2") (pintype "bidirectional"))
    )
    (net (code "87") (name "unconnected-(U1-TST1-Pad39)") (class "Default")
      (node (ref "U1") (pin "39") (pinfunction "TST1_39") (pintype "bidirectional"))
    )
    (net (code "88") (name "unconnected-(U1-TST2-Pad26)") (class "Default")
      (node (ref "U1") (pin "26") (pinfunction "TST2_26") (pintype "bidirectional"))
    )
    (net (code "89") (name "unconnected-(U4B-CLK-Pad11)") (class "Default")
      (node (ref "U4") (pin "11") (pinfunction "CLK_11") (pintype "input"))
    )
    (net (code "90") (name "unconnected-(U4B-CLR-Pad13)") (class "Default")
      (node (ref "U4") (pin "13") (pinfunction "CLR_13") (pintype "input"))
    )
    (net (code "91") (name "unconnected-(U4B-D-Pad12)") (class "Default")
      (node (ref "U4") (pin "12") (pinfunction "D_12") (pintype "input"))
    )
    (net (code "92") (name "unconnected-(U4B-PRE-Pad10)") (class "Default")
      (node (ref "U4") (pin "10") (pinfunction "PRE_10") (pintype "input"))
    )
    (net (code "93") (name "unconnected-(U4B-Q-Pad9)") (class "Default")
      (node (ref "U4") (pin "9") (pinfunction "Q_9") (pintype "output"))
    )
    (net (code "94") (name "unconnected-(U4B-~{Q}-Pad8)") (class "Default")
      (node (ref "U4") (pin "8") (pinfunction "~{Q}_8") (pintype "output"))
    )
    (net (code "95") (name "unconnected-(U6A-I-Pad1)") (class "Default")
      (node (ref "U6") (pin "1") (pinfunction "I_1") (pintype "input"))
    )
    (net (code "96") (name "unconnected-(U6D-I-Pad9)") (class "Default")
      (node (ref "U6") (pin "9") (pinfunction "I_9") (pintype "input"))
    )
    (net (code "97") (name "unconnected-(U6E-I-Pad11)") (class "Default")
      (node (ref "U6") (pin "11") (pinfunction "I_11") (pintype "input"))
    )
    (net (code "98") (name "unconnected-(U6E-O-Pad10)") (class "Default")
      (node (ref "U6") (pin "10") (pinfunction "O_10") (pintype "output"))
    )
    (net (code "99") (name "unconnected-(U7B-I0-Pad5)") (class "Default")
      (node (ref "U7") (pin "5") (pinfunction "I0_5") (pintype "input"))
    )
    (net (code "100") (name "unconnected-(U7B-I1-Pad6)") (class "Default")
      (node (ref "U7") (pin "6") (pinfunction "I1_6") (pintype "input"))
    )
    (net (code "101") (name "unconnected-(U7B-O-Pad4)") (class "Default")
      (node (ref "U7") (pin "4") (pinfunction "O_4") (pintype "output"))
    )
    (net (code "102") (name "Φ") (class "Default")
      (node (ref "J1") (pin "P$8") (pinfunction "X8_P$8") (pintype "bidirectional"))
      (node (ref "J2") (pin "P$8") (pinfunction "X8_P$8") (pintype "bidirectional"))
      (node (ref "U4") (pin "3") (pinfunction "CLK_3") (pintype "input"))
      (node (ref "XC1") (pin "P$8") (pinfunction "X8_P$8") (pintype "bidirectional"))
    )
  )
)
